# usb-power-maker.net
KiCad netlist of a schematic drawn in EAGLE
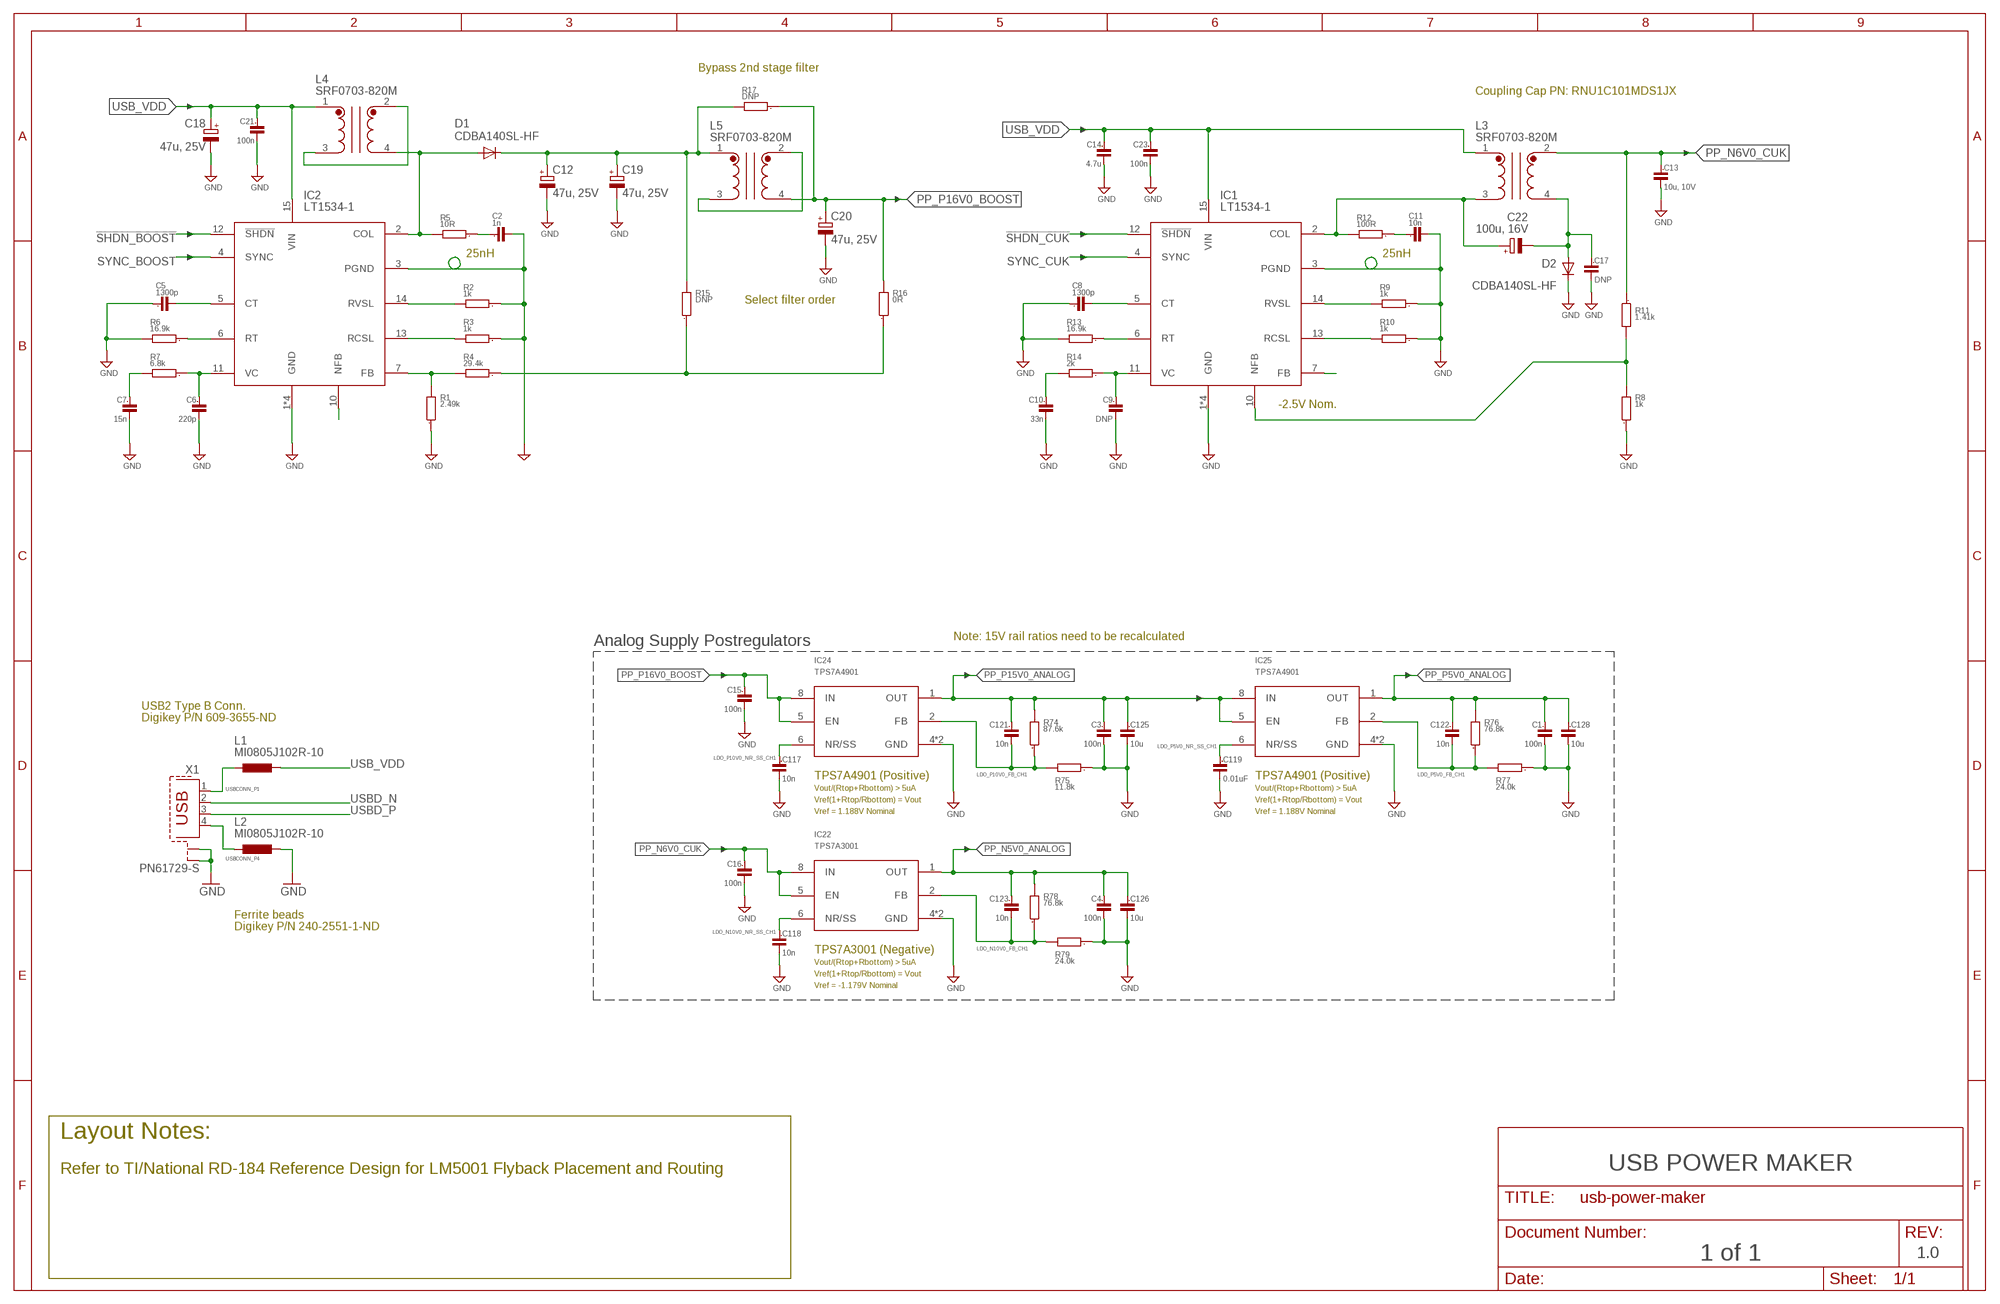
[diagram p0: schematic, sheet 1]

(export (version "E")
  (design (tool "Eeschema 10.0.6"))
  (components
    (comp (ref "C1")
      (value "100n")
      (footprint "eagle-import:0603")
      (libsource (lib "eagle-import") (part "C0603"))
    )
    (comp (ref "C2")
      (value "1n")
      (footprint "eagle-import:0603")
      (libsource (lib "eagle-import") (part "C0603"))
    )
    (comp (ref "C3")
      (value "100n")
      (footprint "eagle-import:0603")
      (libsource (lib "eagle-import") (part "C0603"))
    )
    (comp (ref "C4")
      (value "100n")
      (footprint "eagle-import:0603")
      (libsource (lib "eagle-import") (part "C0603"))
    )
    (comp (ref "C5")
      (value "1300p")
      (footprint "eagle-import:0603")
      (libsource (lib "eagle-import") (part "C0603"))
    )
    (comp (ref "C6")
      (value "220p")
      (footprint "eagle-import:0603")
      (libsource (lib "eagle-import") (part "C0603"))
    )
    (comp (ref "C7")
      (value "15n")
      (footprint "eagle-import:0603")
      (libsource (lib "eagle-import") (part "C0603"))
    )
    (comp (ref "C8")
      (value "1300p")
      (footprint "eagle-import:0603")
      (libsource (lib "eagle-import") (part "C0603"))
    )
    (comp (ref "C9")
      (value "DNP")
      (footprint "eagle-import:0603")
      (libsource (lib "eagle-import") (part "C0603"))
    )
    (comp (ref "C10")
      (value "33n")
      (footprint "eagle-import:0603")
      (libsource (lib "eagle-import") (part "C0603"))
    )
    (comp (ref "C11")
      (value "10n")
      (footprint "eagle-import:0603")
      (libsource (lib "eagle-import") (part "C0603"))
    )
    (comp (ref "C12")
      (value "47u, 25V")
      (footprint "eagle-import:E2,5-6")
      (libsource (lib "eagle-import") (part "CPOL-EUE2.5-6"))
    )
    (comp (ref "C13")
      (value "10u, 10V")
      (footprint "eagle-import:0805")
      (libsource (lib "eagle-import") (part "C0805"))
    )
    (comp (ref "C14")
      (value "4.7u")
      (footprint "eagle-import:0805")
      (libsource (lib "eagle-import") (part "C0805"))
    )
    (comp (ref "C15")
      (value "100n")
      (footprint "eagle-import:0603")
      (libsource (lib "eagle-import") (part "C0603"))
    )
    (comp (ref "C16")
      (value "100n")
      (footprint "eagle-import:0603")
      (libsource (lib "eagle-import") (part "C0603"))
    )
    (comp (ref "C17")
      (value "DNP")
      (footprint "eagle-import:0603")
      (libsource (lib "eagle-import") (part "C0603"))
    )
    (comp (ref "C18")
      (value "47u, 25V")
      (footprint "eagle-import:E2,5-6")
      (libsource (lib "eagle-import") (part "CPOL-EUE2.5-6"))
    )
    (comp (ref "C19")
      (value "47u, 25V")
      (footprint "eagle-import:E2,5-6")
      (libsource (lib "eagle-import") (part "CPOL-EUE2.5-6"))
    )
    (comp (ref "C20")
      (value "47u, 25V")
      (footprint "eagle-import:E2,5-6")
      (libsource (lib "eagle-import") (part "CPOL-EUE2.5-6"))
    )
    (comp (ref "C21")
      (value "100n")
      (footprint "eagle-import:0603")
      (libsource (lib "eagle-import") (part "C0603"))
    )
    (comp (ref "C22")
      (value "100u, 16V")
      (footprint "eagle-import:E2,5-6")
      (libsource (lib "eagle-import") (part "CPOL-EUE2.5-6"))
    )
    (comp (ref "C23")
      (value "100n")
      (footprint "eagle-import:0603")
      (libsource (lib "eagle-import") (part "C0603"))
    )
    (comp (ref "C117")
      (value "10n")
      (footprint "eagle-import:0603")
      (libsource (lib "eagle-import") (part "C0603"))
    )
    (comp (ref "C118")
      (value "10n")
      (footprint "eagle-import:0603")
      (libsource (lib "eagle-import") (part "C0603"))
    )
    (comp (ref "C119")
      (value "0.01uF")
      (footprint "eagle-import:0603")
      (libsource (lib "eagle-import") (part "C0603"))
    )
    (comp (ref "C121")
      (value "10n")
      (footprint "eagle-import:0603")
      (libsource (lib "eagle-import") (part "C0603"))
    )
    (comp (ref "C122")
      (value "10n")
      (footprint "eagle-import:0603")
      (libsource (lib "eagle-import") (part "C0603"))
    )
    (comp (ref "C123")
      (value "10n")
      (footprint "eagle-import:0603")
      (libsource (lib "eagle-import") (part "C0603"))
    )
    (comp (ref "C125")
      (value "10u")
      (footprint "eagle-import:0805")
      (libsource (lib "eagle-import") (part "C0805"))
    )
    (comp (ref "C126")
      (value "10u")
      (footprint "eagle-import:0805")
      (libsource (lib "eagle-import") (part "C0805"))
    )
    (comp (ref "C128")
      (value "10u")
      (footprint "eagle-import:0805")
      (libsource (lib "eagle-import") (part "C0805"))
    )
    (comp (ref "D1")
      (value "CDBA140SL-HF")
      (footprint "eagle-import:DO214AC")
      (libsource (lib "eagle-import") (part "DIODE-DO214AC"))
    )
    (comp (ref "D2")
      (value "CDBA140SL-HF")
      (footprint "eagle-import:DO214AC")
      (libsource (lib "eagle-import") (part "DIODE-DO214AC"))
    )
    (comp (ref "IC1")
      (value "LT1534-1")
      (footprint "eagle-import:SO16")
      (libsource (lib "eagle-import") (part "LT1534"))
    )
    (comp (ref "IC2")
      (value "LT1534-1")
      (footprint "eagle-import:SO16")
      (libsource (lib "eagle-import") (part "LT1534"))
    )
    (comp (ref "IC22")
      (value "TPS7A3001")
      (footprint "eagle-import:MSOP-8_POWER_PAD")
      (libsource (lib "eagle-import") (part "TPS7A"))
    )
    (comp (ref "IC24")
      (value "TPS7A4901")
      (footprint "eagle-import:MSOP-8_POWER_PAD")
      (libsource (lib "eagle-import") (part "TPS7A"))
    )
    (comp (ref "IC25")
      (value "TPS7A4901")
      (footprint "eagle-import:MSOP-8_POWER_PAD")
      (libsource (lib "eagle-import") (part "TPS7A"))
    )
    (comp (ref "L1")
      (value "MI0805J102R-10")
      (footprint "eagle-import:R0805")
      (libsource (lib "eagle-import") (part "INDUCTOR0805"))
    )
    (comp (ref "L2")
      (value "MI0805J102R-10")
      (footprint "eagle-import:R0805")
      (libsource (lib "eagle-import") (part "INDUCTOR0805"))
    )
    (comp (ref "L3")
      (value "SRF0703-820M")
      (footprint "eagle-import:SRF0703")
      (libsource (lib "eagle-import") (part "SRF0703"))
    )
    (comp (ref "L4")
      (value "SRF0703-820M")
      (footprint "eagle-import:SRF0703")
      (libsource (lib "eagle-import") (part "SRF0703"))
    )
    (comp (ref "L5")
      (value "SRF0703-820M")
      (footprint "eagle-import:SRF0703")
      (libsource (lib "eagle-import") (part "SRF0703"))
    )
    (comp (ref "R1")
      (value "2.49k")
      (footprint "eagle-import:0603")
      (libsource (lib "eagle-import") (part "R0603"))
    )
    (comp (ref "R2")
      (value "1k")
      (footprint "eagle-import:0603")
      (libsource (lib "eagle-import") (part "R0603"))
    )
    (comp (ref "R3")
      (value "1k")
      (footprint "eagle-import:0603")
      (libsource (lib "eagle-import") (part "R0603"))
    )
    (comp (ref "R4")
      (value "29.4k")
      (footprint "eagle-import:0603")
      (libsource (lib "eagle-import") (part "R0603"))
    )
    (comp (ref "R5")
      (value "10R")
      (footprint "eagle-import:0603")
      (libsource (lib "eagle-import") (part "R0603"))
    )
    (comp (ref "R6")
      (value "16.9k")
      (footprint "eagle-import:0603")
      (libsource (lib "eagle-import") (part "R0603"))
    )
    (comp (ref "R7")
      (value "6.8k")
      (footprint "eagle-import:0603")
      (libsource (lib "eagle-import") (part "R0603"))
    )
    (comp (ref "R8")
      (value "1k")
      (footprint "eagle-import:0603")
      (libsource (lib "eagle-import") (part "R0603"))
    )
    (comp (ref "R9")
      (value "1k")
      (footprint "eagle-import:0603")
      (libsource (lib "eagle-import") (part "R0603"))
    )
    (comp (ref "R10")
      (value "1k")
      (footprint "eagle-import:0603")
      (libsource (lib "eagle-import") (part "R0603"))
    )
    (comp (ref "R11")
      (value "1.41k")
      (footprint "eagle-import:0603")
      (libsource (lib "eagle-import") (part "R0603"))
    )
    (comp (ref "R12")
      (value "100R")
      (footprint "eagle-import:0603")
      (libsource (lib "eagle-import") (part "R0603"))
    )
    (comp (ref "R13")
      (value "16.9k")
      (footprint "eagle-import:0603")
      (libsource (lib "eagle-import") (part "R0603"))
    )
    (comp (ref "R14")
      (value "2k")
      (footprint "eagle-import:0603")
      (libsource (lib "eagle-import") (part "R0603"))
    )
    (comp (ref "R15")
      (value "DNP")
      (footprint "eagle-import:0603")
      (libsource (lib "eagle-import") (part "R0603"))
    )
    (comp (ref "R16")
      (value "0R")
      (footprint "eagle-import:0603")
      (libsource (lib "eagle-import") (part "R0603"))
    )
    (comp (ref "R17")
      (value "DNP")
      (footprint "eagle-import:0603")
      (libsource (lib "eagle-import") (part "R0603"))
    )
    (comp (ref "R74")
      (value "87.6k")
      (footprint "eagle-import:0603")
      (libsource (lib "eagle-import") (part "R0603"))
    )
    (comp (ref "R75")
      (value "11.8k")
      (footprint "eagle-import:0603")
      (libsource (lib "eagle-import") (part "R0603"))
    )
    (comp (ref "R76")
      (value "76.8k")
      (footprint "eagle-import:0603")
      (libsource (lib "eagle-import") (part "R0603"))
    )
    (comp (ref "R77")
      (value "24.0k")
      (footprint "eagle-import:0603")
      (libsource (lib "eagle-import") (part "R0603"))
    )
    (comp (ref "R78")
      (value "76.8k")
      (footprint "eagle-import:0603")
      (libsource (lib "eagle-import") (part "R0603"))
    )
    (comp (ref "R79")
      (value "24.0k")
      (footprint "eagle-import:0603")
      (libsource (lib "eagle-import") (part "R0603"))
    )
    (comp (ref "X1")
      (value "PN61729-S")
      (footprint "eagle-import:PN61729-S")
      (libsource (lib "eagle-import") (part "PN61729-S"))
    )
  )
  (nets
    (net (code "1") (name "/LDO_N10V0_FB_CH1") (class "Default")
      (node (ref "C123") (pin "2") (pinfunction "2_2") (pintype "passive"))
      (node (ref "IC22") (pin "2") (pinfunction "FB_2") (pintype "bidirectional"))
      (node (ref "R78") (pin "1") (pinfunction "1_1") (pintype "passive"))
      (node (ref "R79") (pin "2") (pinfunction "2_2") (pintype "passive"))
    )
    (net (code "2") (name "/LDO_N10V0_NR_SS_CH1") (class "Default")
      (node (ref "C118") (pin "1") (pinfunction "1_1") (pintype "passive"))
      (node (ref "IC22") (pin "6") (pinfunction "NR/SS_6") (pintype "bidirectional"))
    )
    (net (code "3") (name "/LDO_P5V0_FB_CH1") (class "Default")
      (node (ref "C122") (pin "2") (pinfunction "2_2") (pintype "passive"))
      (node (ref "IC25") (pin "2") (pinfunction "FB_2") (pintype "bidirectional"))
      (node (ref "R76") (pin "1") (pinfunction "1_1") (pintype "passive"))
      (node (ref "R77") (pin "2") (pinfunction "2_2") (pintype "passive"))
    )
    (net (code "4") (name "/LDO_P5V0_NR_SS_CH1") (class "Default")
      (node (ref "C119") (pin "1") (pinfunction "1_1") (pintype "passive"))
      (node (ref "IC25") (pin "6") (pinfunction "NR/SS_6") (pintype "bidirectional"))
    )
    (net (code "5") (name "/LDO_P10V0_FB_CH1") (class "Default")
      (node (ref "C121") (pin "2") (pinfunction "2_2") (pintype "passive"))
      (node (ref "IC24") (pin "2") (pinfunction "FB_2") (pintype "bidirectional"))
      (node (ref "R74") (pin "1") (pinfunction "1_1") (pintype "passive"))
      (node (ref "R75") (pin "2") (pinfunction "2_2") (pintype "passive"))
    )
    (net (code "6") (name "/LDO_P10V0_NR_SS_CH1") (class "Default")
      (node (ref "C117") (pin "1") (pinfunction "1_1") (pintype "passive"))
      (node (ref "IC24") (pin "6") (pinfunction "NR/SS_6") (pintype "bidirectional"))
    )
    (net (code "7") (name "/SYNC_BOOST") (class "Default")
      (node (ref "IC2") (pin "4") (pinfunction "SYNC_4") (pintype "bidirectional"))
    )
    (net (code "8") (name "/SYNC_CUK") (class "Default")
      (node (ref "IC1") (pin "4") (pinfunction "SYNC_4") (pintype "bidirectional"))
    )
    (net (code "9") (name "/USBCONN_P1") (class "Default")
      (node (ref "L1") (pin "1") (pinfunction "P$1_1") (pintype "bidirectional"))
      (node (ref "X1") (pin "1") (pinfunction "1_1") (pintype "passive"))
    )
    (net (code "10") (name "/USBCONN_P4") (class "Default")
      (node (ref "L2") (pin "1") (pinfunction "P$1_1") (pintype "bidirectional"))
      (node (ref "X1") (pin "4") (pinfunction "4_4") (pintype "passive"))
    )
    (net (code "11") (name "/USBD_N") (class "Default")
      (node (ref "X1") (pin "2") (pinfunction "2_2") (pintype "passive"))
    )
    (net (code "12") (name "/USBD_P") (class "Default")
      (node (ref "X1") (pin "3") (pinfunction "3_3") (pintype "passive"))
    )
    (net (code "13") (name "/~{SHDN_BOOST}") (class "Default")
      (node (ref "IC2") (pin "12") (pinfunction "~{SHDN}_12") (pintype "bidirectional"))
    )
    (net (code "14") (name "/~{SHDN_CUK}") (class "Default")
      (node (ref "IC1") (pin "12") (pinfunction "~{SHDN}_12") (pintype "bidirectional"))
    )
    (net (code "15") (name "GND") (class "Default")
      (node (ref "C1") (pin "2") (pinfunction "2_2") (pintype "passive"))
      (node (ref "C10") (pin "2") (pinfunction "2_2") (pintype "passive"))
      (node (ref "C11") (pin "2") (pinfunction "2_2") (pintype "passive"))
      (node (ref "C117") (pin "2") (pinfunction "2_2") (pintype "passive"))
      (node (ref "C118") (pin "2") (pinfunction "2_2") (pintype "passive"))
      (node (ref "C119") (pin "2") (pinfunction "2_2") (pintype "passive"))
      (node (ref "C12") (pin "-") (pinfunction "-_-") (pintype "passive"))
      (node (ref "C125") (pin "2") (pinfunction "2_2") (pintype "passive"))
      (node (ref "C126") (pin "2") (pinfunction "2_2") (pintype "passive"))
      (node (ref "C128") (pin "2") (pinfunction "2_2") (pintype "passive"))
      (node (ref "C13") (pin "2") (pinfunction "2_2") (pintype "passive"))
      (node (ref "C14") (pin "2") (pinfunction "2_2") (pintype "passive"))
      (node (ref "C15") (pin "2") (pinfunction "2_2") (pintype "passive"))
      (node (ref "C16") (pin "2") (pinfunction "2_2") (pintype "passive"))
      (node (ref "C17") (pin "2") (pinfunction "2_2") (pintype "passive"))
      (node (ref "C18") (pin "-") (pinfunction "-_-") (pintype "passive"))
      (node (ref "C19") (pin "-") (pinfunction "-_-") (pintype "passive"))
      (node (ref "C2") (pin "2") (pinfunction "2_2") (pintype "passive"))
      (node (ref "C20") (pin "-") (pinfunction "-_-") (pintype "passive"))
      (node (ref "C21") (pin "2") (pinfunction "2_2") (pintype "passive"))
      (node (ref "C23") (pin "2") (pinfunction "2_2") (pintype "passive"))
      (node (ref "C3") (pin "2") (pinfunction "2_2") (pintype "passive"))
      (node (ref "C4") (pin "2") (pinfunction "2_2") (pintype "passive"))
      (node (ref "C5") (pin "1") (pinfunction "1_1") (pintype "passive"))
      (node (ref "C6") (pin "2") (pinfunction "2_2") (pintype "passive"))
      (node (ref "C7") (pin "2") (pinfunction "2_2") (pintype "passive"))
      (node (ref "C8") (pin "1") (pinfunction "1_1") (pintype "passive"))
      (node (ref "C9") (pin "2") (pinfunction "2_2") (pintype "passive"))
      (node (ref "D2") (pin "C") (pinfunction "C_C") (pintype "passive"))
      (node (ref "IC1") (pin "1") (pinfunction "GND_1") (pintype "bidirectional"))
      (node (ref "IC1") (pin "16") (pinfunction "GND_16") (pintype "bidirectional"))
      (node (ref "IC1") (pin "3") (pinfunction "PGND_3") (pintype "bidirectional"))
      (node (ref "IC1") (pin "8") (pinfunction "GND_8") (pintype "bidirectional"))
      (node (ref "IC1") (pin "9") (pinfunction "GND_9") (pintype "bidirectional"))
      (node (ref "IC2") (pin "1") (pinfunction "GND_1") (pintype "bidirectional"))
      (node (ref "IC2") (pin "16") (pinfunction "GND_16") (pintype "bidirectional"))
      (node (ref "IC2") (pin "3") (pinfunction "PGND_3") (pintype "bidirectional"))
      (node (ref "IC2") (pin "8") (pinfunction "GND_8") (pintype "bidirectional"))
      (node (ref "IC2") (pin "9") (pinfunction "GND_9") (pintype "bidirectional"))
      (node (ref "IC22") (pin "4") (pinfunction "GND_4") (pintype "bidirectional"))
      (node (ref "IC22") (pin "PAD") (pinfunction "GND_PAD") (pintype "bidirectional"))
      (node (ref "IC24") (pin "4") (pinfunction "GND_4") (pintype "bidirectional"))
      (node (ref "IC24") (pin "PAD") (pinfunction "GND_PAD") (pintype "bidirectional"))
      (node (ref "IC25") (pin "4") (pinfunction "GND_4") (pintype "bidirectional"))
      (node (ref "IC25") (pin "PAD") (pinfunction "GND_PAD") (pintype "bidirectional"))
      (node (ref "L2") (pin "2") (pinfunction "P$2_2") (pintype "bidirectional"))
      (node (ref "R1") (pin "1") (pinfunction "1_1") (pintype "passive"))
      (node (ref "R10") (pin "1") (pinfunction "1_1") (pintype "passive"))
      (node (ref "R13") (pin "2") (pinfunction "2_2") (pintype "passive"))
      (node (ref "R2") (pin "1") (pinfunction "1_1") (pintype "passive"))
      (node (ref "R3") (pin "1") (pinfunction "1_1") (pintype "passive"))
      (node (ref "R6") (pin "2") (pinfunction "2_2") (pintype "passive"))
      (node (ref "R75") (pin "1") (pinfunction "1_1") (pintype "passive"))
      (node (ref "R77") (pin "1") (pinfunction "1_1") (pintype "passive"))
      (node (ref "R79") (pin "1") (pinfunction "1_1") (pintype "passive"))
      (node (ref "R8") (pin "1") (pinfunction "1_1") (pintype "passive"))
      (node (ref "R9") (pin "1") (pinfunction "1_1") (pintype "passive"))
      (node (ref "X1") (pin "S1") (pinfunction "S1_S1") (pintype "passive"))
      (node (ref "X1") (pin "S2") (pinfunction "S2_S2") (pintype "passive"))
    )
    (net (code "16") (name "Net-(C2-Pad1)") (class "Default")
      (node (ref "C2") (pin "1") (pinfunction "1_1") (pintype "passive"))
      (node (ref "R5") (pin "1") (pinfunction "1_1") (pintype "passive"))
    )
    (net (code "17") (name "Net-(C7-Pad1)") (class "Default")
      (node (ref "C7") (pin "1") (pinfunction "1_1") (pintype "passive"))
      (node (ref "R7") (pin "2") (pinfunction "2_2") (pintype "passive"))
    )
    (net (code "18") (name "Net-(C10-Pad1)") (class "Default")
      (node (ref "C10") (pin "1") (pinfunction "1_1") (pintype "passive"))
      (node (ref "R14") (pin "2") (pinfunction "2_2") (pintype "passive"))
    )
    (net (code "19") (name "Net-(C11-Pad1)") (class "Default")
      (node (ref "C11") (pin "1") (pinfunction "1_1") (pintype "passive"))
      (node (ref "R12") (pin "1") (pinfunction "1_1") (pintype "passive"))
    )
    (net (code "20") (name "Net-(C12-Pad+)") (class "Default")
      (node (ref "C12") (pin "+") (pinfunction "+_+") (pintype "passive"))
      (node (ref "C19") (pin "+") (pinfunction "+_+") (pintype "passive"))
      (node (ref "D1") (pin "C") (pinfunction "C_C") (pintype "passive"))
      (node (ref "L5") (pin "1") (pinfunction "1_1") (pintype "bidirectional"))
      (node (ref "R15") (pin "2") (pinfunction "2_2") (pintype "passive"))
      (node (ref "R17") (pin "2") (pinfunction "2_2") (pintype "passive"))
    )
    (net (code "21") (name "Net-(C17-Pad1)") (class "Default")
      (node (ref "C17") (pin "1") (pinfunction "1_1") (pintype "passive"))
      (node (ref "C22") (pin "-") (pinfunction "-_-") (pintype "passive"))
      (node (ref "D2") (pin "A") (pinfunction "A_A") (pintype "passive"))
      (node (ref "L3") (pin "4") (pinfunction "4_4") (pintype "bidirectional"))
    )
    (net (code "22") (name "Net-(IC1-COL)") (class "Default")
      (node (ref "C22") (pin "+") (pinfunction "+_+") (pintype "passive"))
      (node (ref "IC1") (pin "2") (pinfunction "COL_2") (pintype "bidirectional"))
      (node (ref "L3") (pin "3") (pinfunction "3_3") (pintype "bidirectional"))
      (node (ref "R12") (pin "2") (pinfunction "2_2") (pintype "passive"))
    )
    (net (code "23") (name "Net-(IC1-CT)") (class "Default")
      (node (ref "C8") (pin "2") (pinfunction "2_2") (pintype "passive"))
      (node (ref "IC1") (pin "5") (pinfunction "CT_5") (pintype "bidirectional"))
    )
    (net (code "24") (name "Net-(IC1-NFB)") (class "Default")
      (node (ref "IC1") (pin "10") (pinfunction "NFB_10") (pintype "bidirectional"))
      (node (ref "R11") (pin "2") (pinfunction "2_2") (pintype "passive"))
      (node (ref "R8") (pin "2") (pinfunction "2_2") (pintype "passive"))
    )
    (net (code "25") (name "Net-(IC1-RCSL)") (class "Default")
      (node (ref "IC1") (pin "13") (pinfunction "RCSL_13") (pintype "bidirectional"))
      (node (ref "R10") (pin "2") (pinfunction "2_2") (pintype "passive"))
    )
    (net (code "26") (name "Net-(IC1-RT)") (class "Default")
      (node (ref "IC1") (pin "6") (pinfunction "RT_6") (pintype "bidirectional"))
      (node (ref "R13") (pin "1") (pinfunction "1_1") (pintype "passive"))
    )
    (net (code "27") (name "Net-(IC1-RVSL)") (class "Default")
      (node (ref "IC1") (pin "14") (pinfunction "RVSL_14") (pintype "bidirectional"))
      (node (ref "R9") (pin "2") (pinfunction "2_2") (pintype "passive"))
    )
    (net (code "28") (name "Net-(IC1-VC)") (class "Default")
      (node (ref "C9") (pin "1") (pinfunction "1_1") (pintype "passive"))
      (node (ref "IC1") (pin "11") (pinfunction "VC_11") (pintype "bidirectional"))
      (node (ref "R14") (pin "1") (pinfunction "1_1") (pintype "passive"))
    )
    (net (code "29") (name "Net-(IC2-COL)") (class "Default")
      (node (ref "D1") (pin "A") (pinfunction "A_A") (pintype "passive"))
      (node (ref "IC2") (pin "2") (pinfunction "COL_2") (pintype "bidirectional"))
      (node (ref "L4") (pin "4") (pinfunction "4_4") (pintype "bidirectional"))
      (node (ref "R5") (pin "2") (pinfunction "2_2") (pintype "passive"))
    )
    (net (code "30") (name "Net-(IC2-CT)") (class "Default")
      (node (ref "C5") (pin "2") (pinfunction "2_2") (pintype "passive"))
      (node (ref "IC2") (pin "5") (pinfunction "CT_5") (pintype "bidirectional"))
    )
    (net (code "31") (name "Net-(IC2-FB)") (class "Default")
      (node (ref "IC2") (pin "7") (pinfunction "FB_7") (pintype "bidirectional"))
      (node (ref "R1") (pin "2") (pinfunction "2_2") (pintype "passive"))
      (node (ref "R4") (pin "2") (pinfunction "2_2") (pintype "passive"))
    )
    (net (code "32") (name "Net-(IC2-RCSL)") (class "Default")
      (node (ref "IC2") (pin "13") (pinfunction "RCSL_13") (pintype "bidirectional"))
      (node (ref "R3") (pin "2") (pinfunction "2_2") (pintype "passive"))
    )
    (net (code "33") (name "Net-(IC2-RT)") (class "Default")
      (node (ref "IC2") (pin "6") (pinfunction "RT_6") (pintype "bidirectional"))
      (node (ref "R6") (pin "1") (pinfunction "1_1") (pintype "passive"))
    )
    (net (code "34") (name "Net-(IC2-RVSL)") (class "Default")
      (node (ref "IC2") (pin "14") (pinfunction "RVSL_14") (pintype "bidirectional"))
      (node (ref "R2") (pin "2") (pinfunction "2_2") (pintype "passive"))
    )
    (net (code "35") (name "Net-(IC2-VC)") (class "Default")
      (node (ref "C6") (pin "1") (pinfunction "1_1") (pintype "passive"))
      (node (ref "IC2") (pin "11") (pinfunction "VC_11") (pintype "bidirectional"))
      (node (ref "R7") (pin "1") (pinfunction "1_1") (pintype "passive"))
    )
    (net (code "36") (name "Net-(L4-Pad2)") (class "Default")
      (node (ref "L4") (pin "2") (pinfunction "2_2") (pintype "bidirectional"))
      (node (ref "L4") (pin "3") (pinfunction "3_3") (pintype "bidirectional"))
    )
    (net (code "37") (name "Net-(L5-Pad2)") (class "Default")
      (node (ref "L5") (pin "2") (pinfunction "2_2") (pintype "bidirectional"))
      (node (ref "L5") (pin "3") (pinfunction "3_3") (pintype "bidirectional"))
    )
    (net (code "38") (name "Net-(R15-Pad1)") (class "Default")
      (node (ref "R15") (pin "1") (pinfunction "1_1") (pintype "passive"))
      (node (ref "R16") (pin "1") (pinfunction "1_1") (pintype "passive"))
      (node (ref "R4") (pin "1") (pinfunction "1_1") (pintype "passive"))
    )
    (net (code "39") (name "PP_N5V0_ANALOG") (class "Default")
      (node (ref "C123") (pin "1") (pinfunction "1_1") (pintype "passive"))
      (node (ref "C126") (pin "1") (pinfunction "1_1") (pintype "passive"))
      (node (ref "C4") (pin "1") (pinfunction "1_1") (pintype "passive"))
      (node (ref "IC22") (pin "1") (pinfunction "OUT_1") (pintype "bidirectional"))
      (node (ref "R78") (pin "2") (pinfunction "2_2") (pintype "passive"))
    )
    (net (code "40") (name "PP_N6V0_CUK") (class "Default")
      (node (ref "C13") (pin "1") (pinfunction "1_1") (pintype "passive"))
      (node (ref "C16") (pin "1") (pinfunction "1_1") (pintype "passive"))
      (node (ref "IC22") (pin "5") (pinfunction "EN_5") (pintype "bidirectional"))
      (node (ref "IC22") (pin "8") (pinfunction "IN_8") (pintype "bidirectional"))
      (node (ref "L3") (pin "2") (pinfunction "2_2") (pintype "bidirectional"))
      (node (ref "R11") (pin "1") (pinfunction "1_1") (pintype "passive"))
    )
    (net (code "41") (name "PP_P5V0_ANALOG") (class "Default")
      (node (ref "C1") (pin "1") (pinfunction "1_1") (pintype "passive"))
      (node (ref "C122") (pin "1") (pinfunction "1_1") (pintype "passive"))
      (node (ref "C128") (pin "1") (pinfunction "1_1") (pintype "passive"))
      (node (ref "IC25") (pin "1") (pinfunction "OUT_1") (pintype "bidirectional"))
      (node (ref "R76") (pin "2") (pinfunction "2_2") (pintype "passive"))
    )
    (net (code "42") (name "PP_P15V0_ANALOG") (class "Default")
      (node (ref "C121") (pin "1") (pinfunction "1_1") (pintype "passive"))
      (node (ref "C125") (pin "1") (pinfunction "1_1") (pintype "passive"))
      (node (ref "C3") (pin "1") (pinfunction "1_1") (pintype "passive"))
      (node (ref "IC24") (pin "1") (pinfunction "OUT_1") (pintype "bidirectional"))
      (node (ref "IC25") (pin "5") (pinfunction "EN_5") (pintype "bidirectional"))
      (node (ref "IC25") (pin "8") (pinfunction "IN_8") (pintype "bidirectional"))
      (node (ref "R74") (pin "2") (pinfunction "2_2") (pintype "passive"))
    )
    (net (code "43") (name "PP_P16V0_BOOST") (class "Default")
      (node (ref "C15") (pin "1") (pinfunction "1_1") (pintype "passive"))
      (node (ref "C20") (pin "+") (pinfunction "+_+") (pintype "passive"))
      (node (ref "IC24") (pin "5") (pinfunction "EN_5") (pintype "bidirectional"))
      (node (ref "IC24") (pin "8") (pinfunction "IN_8") (pintype "bidirectional"))
      (node (ref "L5") (pin "4") (pinfunction "4_4") (pintype "bidirectional"))
      (node (ref "R16") (pin "2") (pinfunction "2_2") (pintype "passive"))
      (node (ref "R17") (pin "1") (pinfunction "1_1") (pintype "passive"))
    )
    (net (code "44") (name "USB_VDD") (class "Default")
      (node (ref "C14") (pin "1") (pinfunction "1_1") (pintype "passive"))
      (node (ref "C18") (pin "+") (pinfunction "+_+") (pintype "passive"))
      (node (ref "C21") (pin "1") (pinfunction "1_1") (pintype "passive"))
      (node (ref "C23") (pin "1") (pinfunction "1_1") (pintype "passive"))
      (node (ref "IC1") (pin "15") (pinfunction "VIN_15") (pintype "bidirectional"))
      (node (ref "IC2") (pin "15") (pinfunction "VIN_15") (pintype "bidirectional"))
      (node (ref "L1") (pin "2") (pinfunction "P$2_2") (pintype "bidirectional"))
      (node (ref "L3") (pin "1") (pinfunction "1_1") (pintype "bidirectional"))
      (node (ref "L4") (pin "1") (pinfunction "1_1") (pintype "bidirectional"))
    )
    (net (code "45") (name "unconnected-(IC1-FB-Pad7)") (class "Default")
      (node (ref "IC1") (pin "7") (pinfunction "FB_7") (pintype "bidirectional"))
    )
    (net (code "46") (name "unconnected-(IC2-NFB-Pad10)") (class "Default")
      (node (ref "IC2") (pin "10") (pinfunction "NFB_10") (pintype "bidirectional"))
    )
  )
)
